# MCU_Debug.net
KiCad netlist of a schematic drawn in Altium Designer
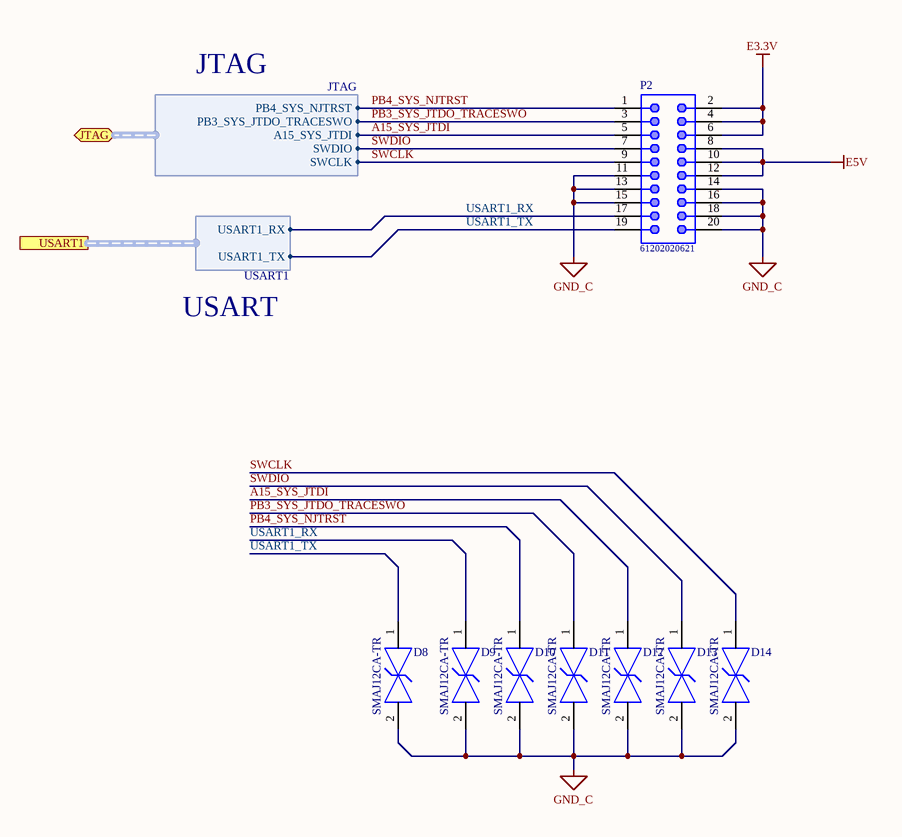
[diagram p0: MCU_Debug.SchDoc]

(export (version "E")
  (design (tool "Eeschema 10.0.6"))
  (components
    (comp (ref "D8")
      (value "SMAJ12CA-TR")
      (footprint "FP-SMA-CA-MFG")
      (description "25.3V Clamp 91A (8/20µs) Ipp Tvs Diode Surface Mount SMA (DO-214AC)")
      (fields (field (name "OCTOPART") "https://octopart.com/smaj12ca-tr-stmicroelectronics-347060"))
      (libsource (lib "Altium Content Vault") (part "876f4347bf90aa6f500f43e3cd03972"))
    )
    (comp (ref "D9")
      (value "SMAJ12CA-TR")
      (footprint "FP-SMA-CA-MFG")
      (description "25.3V Clamp 91A (8/20µs) Ipp Tvs Diode Surface Mount SMA (DO-214AC)")
      (fields (field (name "OCTOPART") "https://octopart.com/smaj12ca-tr-stmicroelectronics-347060"))
      (libsource (lib "Altium Content Vault") (part "876f4347bf90aa6f500f43e3cd03972"))
    )
    (comp (ref "D10")
      (value "SMAJ12CA-TR")
      (footprint "FP-SMA-CA-MFG")
      (description "25.3V Clamp 91A (8/20µs) Ipp Tvs Diode Surface Mount SMA (DO-214AC)")
      (fields (field (name "OCTOPART") "https://octopart.com/smaj12ca-tr-stmicroelectronics-347060"))
      (libsource (lib "Altium Content Vault") (part "876f4347bf90aa6f500f43e3cd03972"))
    )
    (comp (ref "D11")
      (value "SMAJ12CA-TR")
      (footprint "FP-SMA-CA-MFG")
      (description "25.3V Clamp 91A (8/20µs) Ipp Tvs Diode Surface Mount SMA (DO-214AC)")
      (fields (field (name "OCTOPART") "https://octopart.com/smaj12ca-tr-stmicroelectronics-347060"))
      (libsource (lib "Altium Content Vault") (part "876f4347bf90aa6f500f43e3cd03972"))
    )
    (comp (ref "D12")
      (value "SMAJ12CA-TR")
      (footprint "FP-SMA-CA-MFG")
      (description "25.3V Clamp 91A (8/20µs) Ipp Tvs Diode Surface Mount SMA (DO-214AC)")
      (fields (field (name "OCTOPART") "https://octopart.com/smaj12ca-tr-stmicroelectronics-347060"))
      (libsource (lib "Altium Content Vault") (part "876f4347bf90aa6f500f43e3cd03972"))
    )
    (comp (ref "D13")
      (value "SMAJ12CA-TR")
      (footprint "FP-SMA-CA-MFG")
      (description "25.3V Clamp 91A (8/20µs) Ipp Tvs Diode Surface Mount SMA (DO-214AC)")
      (fields (field (name "OCTOPART") "https://octopart.com/smaj12ca-tr-stmicroelectronics-347060"))
      (libsource (lib "Altium Content Vault") (part "876f4347bf90aa6f500f43e3cd03972"))
    )
    (comp (ref "D14")
      (value "SMAJ12CA-TR")
      (footprint "FP-SMA-CA-MFG")
      (description "25.3V Clamp 91A (8/20µs) Ipp Tvs Diode Surface Mount SMA (DO-214AC)")
      (fields (field (name "OCTOPART") "https://octopart.com/smaj12ca-tr-stmicroelectronics-347060"))
      (libsource (lib "Altium Content Vault") (part "876f4347bf90aa6f500f43e3cd03972"))
    )
    (comp (ref "P2")
      (value "61202020621")
      (footprint "61202020621")
      (description "Male Box Header WR-BHD, SMT, Vertical, pitch 2.54 mm, 20 pins")
      (fields (field (name "PUBLISHER") "Wurth Elektronik"))
      (libsource (lib "o162711v243 Altium_WR-BHD (rev19a)") (part "61202020621"))
    )
  )
  (nets
    (net (code "3") (name "/A15_SYS_JTDI") (class "Default")
      (node (ref "D12") (pin "1") (pinfunction "1_1") (pintype "passive"))
      (node (ref "P2") (pin "5") (pinfunction "5_5") (pintype "passive"))
    )
    (net (code "4") (name "/PB3_SYS_JTDO_TRACESWO") (class "Default")
      (node (ref "D11") (pin "1") (pinfunction "1_1") (pintype "passive"))
      (node (ref "P2") (pin "3") (pinfunction "3_3") (pintype "passive"))
    )
    (net (code "5") (name "/PB4_SYS_NJTRST") (class "Default")
      (node (ref "D10") (pin "1") (pinfunction "1_1") (pintype "passive"))
      (node (ref "P2") (pin "1") (pinfunction "1_1") (pintype "passive"))
    )
    (net (code "6") (name "/SWCLK") (class "Default")
      (node (ref "D14") (pin "1") (pinfunction "1_1") (pintype "passive"))
      (node (ref "P2") (pin "9") (pinfunction "9_9") (pintype "passive"))
    )
    (net (code "7") (name "/SWDIO") (class "Default")
      (node (ref "D13") (pin "1") (pinfunction "1_1") (pintype "passive"))
      (node (ref "P2") (pin "7") (pinfunction "7_7") (pintype "passive"))
    )
    (net (code "8") (name "/USART1_RX") (class "Default")
      (node (ref "D9") (pin "1") (pinfunction "1_1") (pintype "passive"))
      (node (ref "P2") (pin "17") (pinfunction "17_17") (pintype "passive"))
    )
    (net (code "9") (name "/USART1_TX") (class "Default")
      (node (ref "D8") (pin "1") (pinfunction "1_1") (pintype "passive"))
      (node (ref "P2") (pin "19") (pinfunction "19_19") (pintype "passive"))
    )
    (net (code "12") (name "E3.3V") (class "Default")
      (node (ref "P2") (pin "2") (pinfunction "2_2") (pintype "passive"))
      (node (ref "P2") (pin "4") (pinfunction "4_4") (pintype "passive"))
      (node (ref "P2") (pin "6") (pinfunction "6_6") (pintype "passive"))
    )
    (net (code "13") (name "E5V") (class "Default")
      (node (ref "P2") (pin "10") (pinfunction "10_10") (pintype "passive"))
      (node (ref "P2") (pin "12") (pinfunction "12_12") (pintype "passive"))
      (node (ref "P2") (pin "8") (pinfunction "8_8") (pintype "passive"))
    )
    (net (code "14") (name "GND_C") (class "Default")
      (node (ref "D10") (pin "2") (pinfunction "2_2") (pintype "passive"))
      (node (ref "D11") (pin "2") (pinfunction "2_2") (pintype "passive"))
      (node (ref "D12") (pin "2") (pinfunction "2_2") (pintype "passive"))
      (node (ref "D13") (pin "2") (pinfunction "2_2") (pintype "passive"))
      (node (ref "D14") (pin "2") (pinfunction "2_2") (pintype "passive"))
      (node (ref "D8") (pin "2") (pinfunction "2_2") (pintype "passive"))
      (node (ref "D9") (pin "2") (pinfunction "2_2") (pintype "passive"))
      (node (ref "P2") (pin "11") (pinfunction "11_11") (pintype "passive"))
      (node (ref "P2") (pin "13") (pinfunction "13_13") (pintype "passive"))
      (node (ref "P2") (pin "14") (pinfunction "14_14") (pintype "passive"))
      (node (ref "P2") (pin "15") (pinfunction "15_15") (pintype "passive"))
      (node (ref "P2") (pin "16") (pinfunction "16_16") (pintype "passive"))
      (node (ref "P2") (pin "18") (pinfunction "18_18") (pintype "passive"))
      (node (ref "P2") (pin "20") (pinfunction "20_20") (pintype "passive"))
    )
  )
)
